# TSOC_USBUART2_R3_0.net
KiCad netlist of a schematic drawn in EAGLE
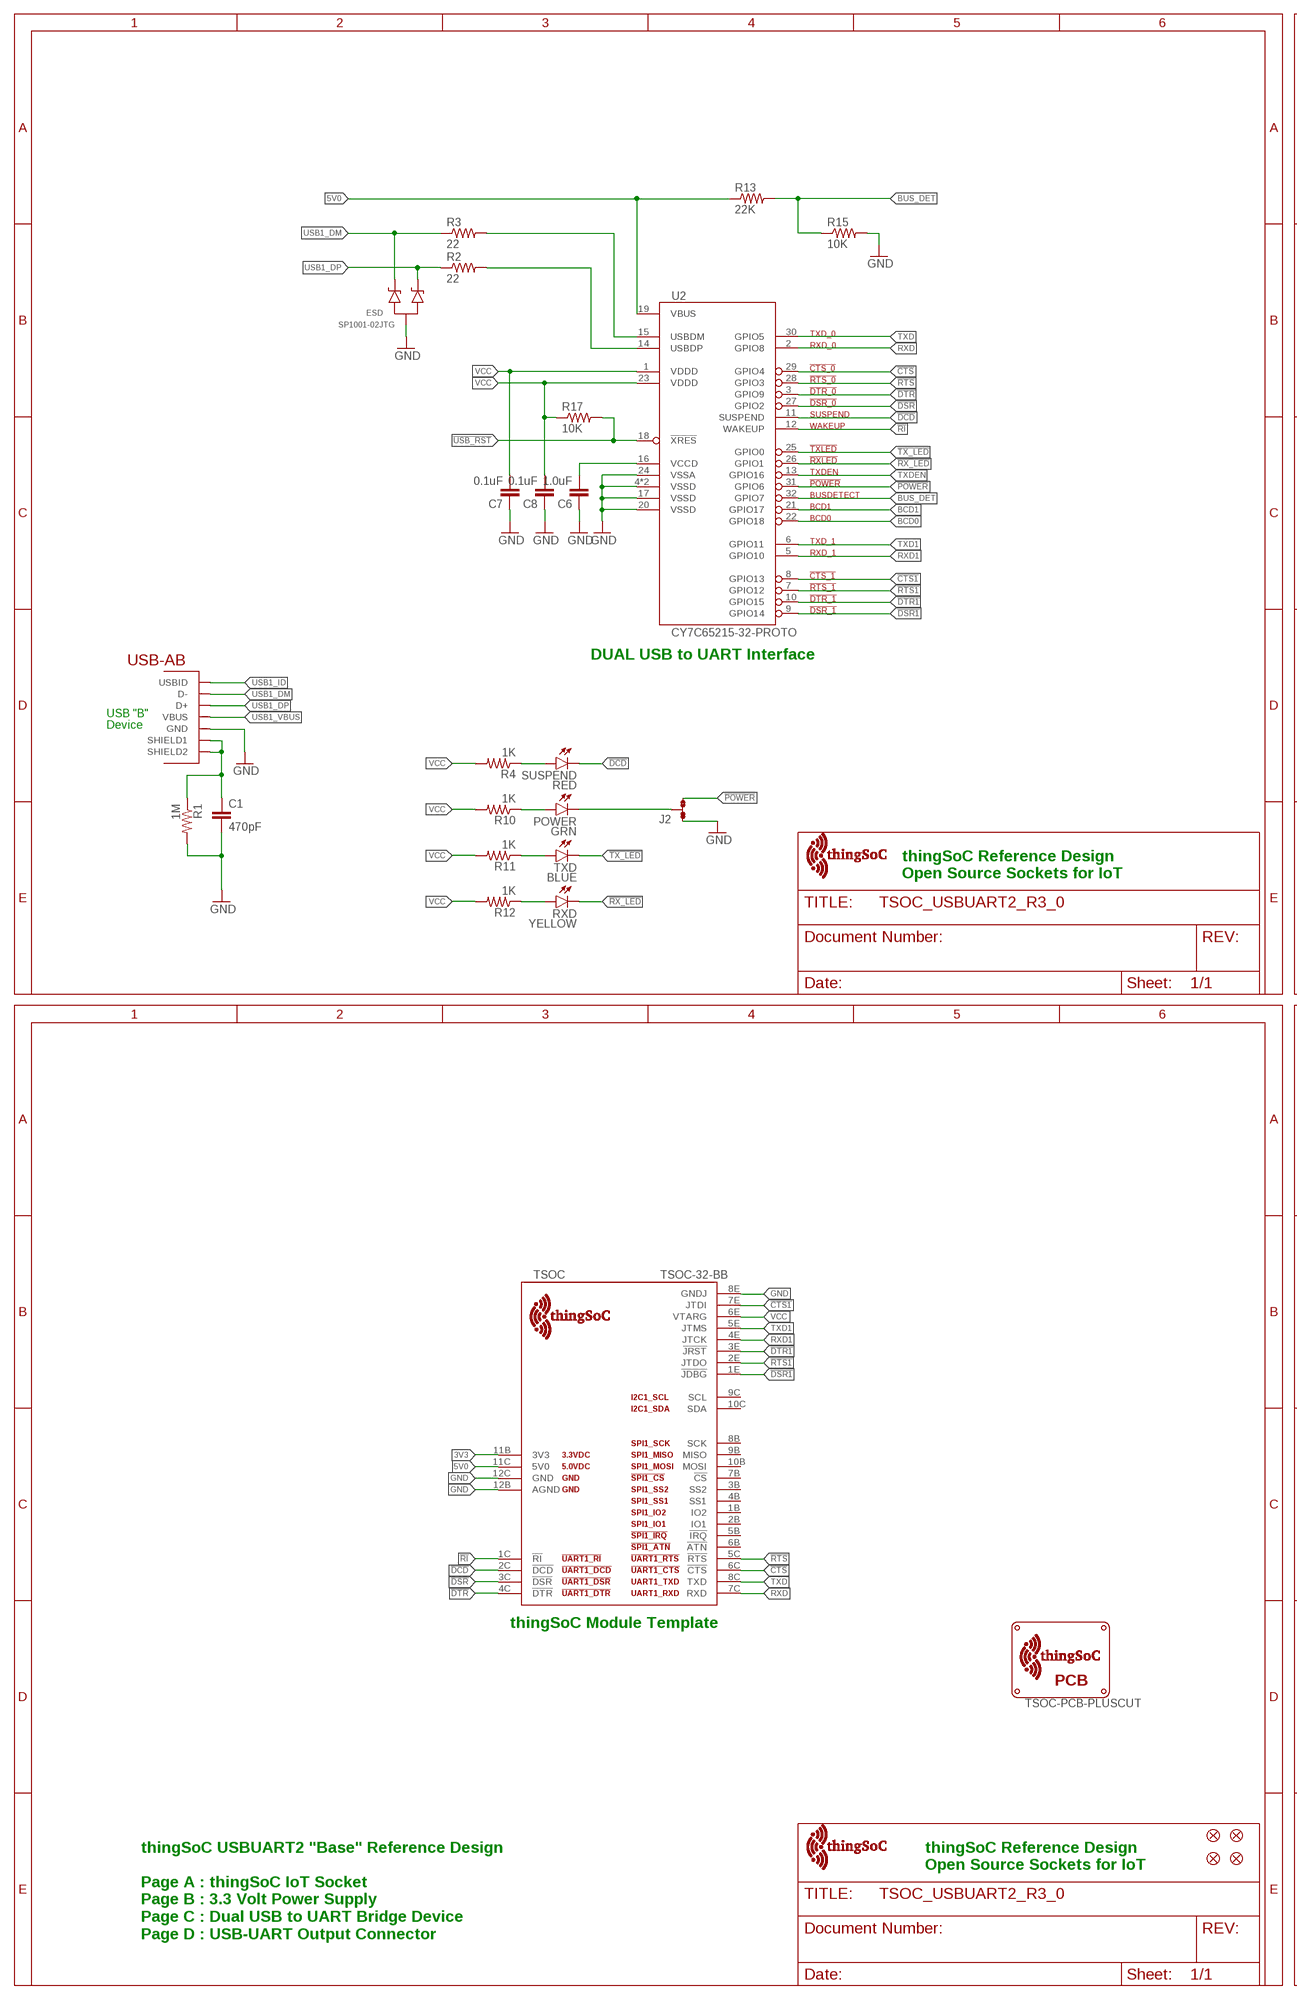
[diagram p0: schematic, sheet 1, part 1 of 2]
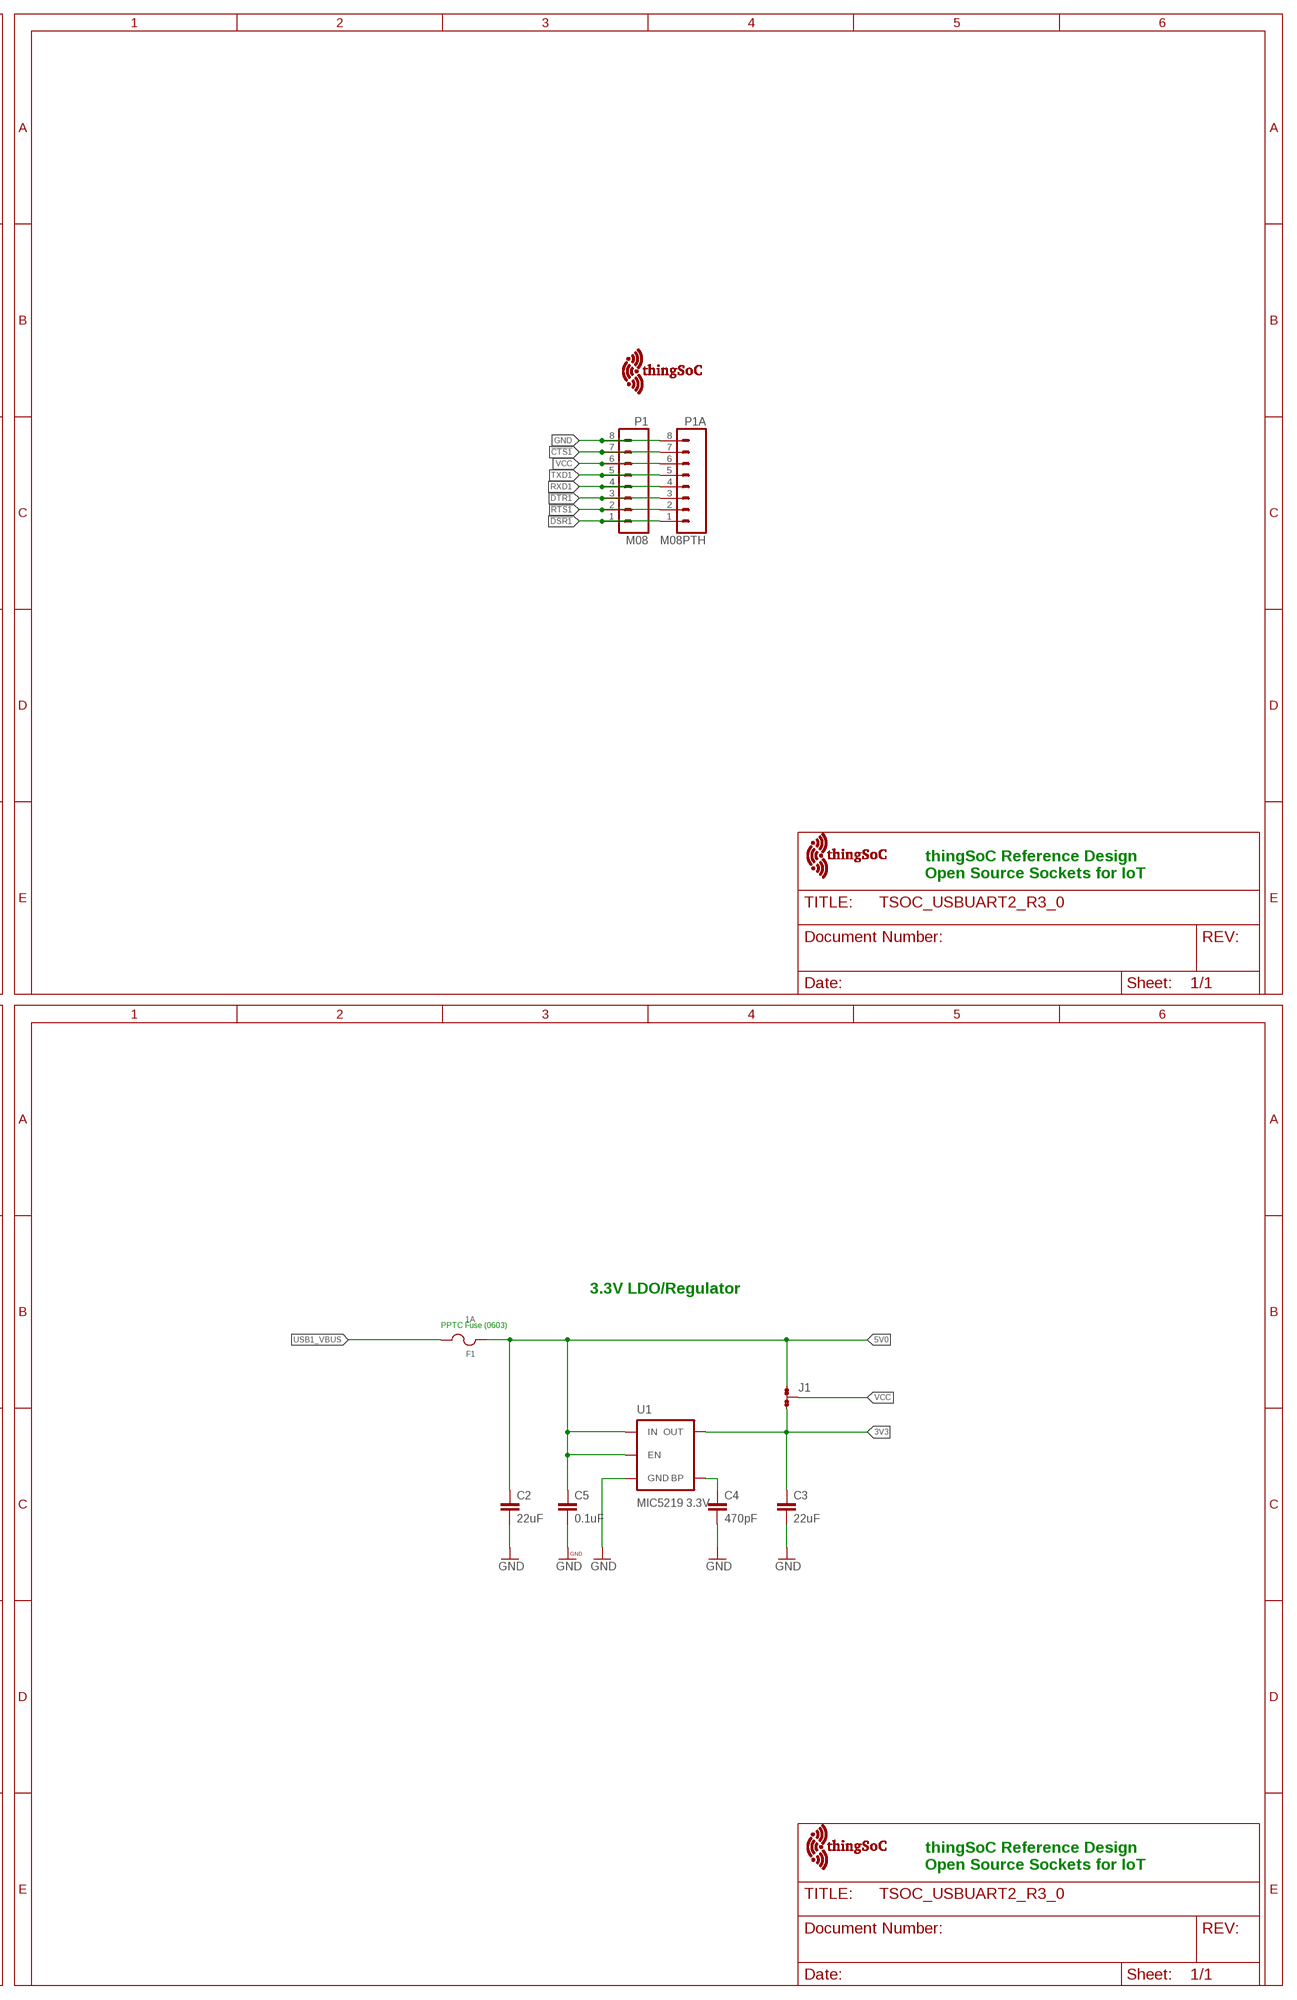
[diagram p1: schematic, sheet 1, part 2 of 2]

(export (version "E")
  (design (tool "Eeschema 10.0.6"))
  (components
    (comp (ref "C1")
      (value "470pF")
      (footprint "eagle-import:EIA-0603")
      (libsource (lib "eagle-import") (part "CAP-0603"))
    )
    (comp (ref "C2")
      (value "22uF")
      (footprint "eagle-import:EIA-1206")
      (libsource (lib "eagle-import") (part "CAP-1206"))
    )
    (comp (ref "C3")
      (value "22uF")
      (footprint "eagle-import:EIA-1206")
      (libsource (lib "eagle-import") (part "CAP-1206"))
    )
    (comp (ref "C4")
      (value "470pF")
      (footprint "eagle-import:EIA-0603")
      (libsource (lib "eagle-import") (part "CAP-0603"))
    )
    (comp (ref "C5")
      (value "0.1uF")
      (footprint "eagle-import:EIA-0603")
      (libsource (lib "eagle-import") (part "CAP-0603"))
    )
    (comp (ref "C6")
      (value "1.0uF")
      (footprint "eagle-import:EIA-0603")
      (libsource (lib "eagle-import") (part "CAP-0603"))
    )
    (comp (ref "C7")
      (value "0.1uF")
      (footprint "eagle-import:EIA-0603")
      (libsource (lib "eagle-import") (part "CAP-0603"))
    )
    (comp (ref "C8")
      (value "0.1uF")
      (footprint "eagle-import:EIA-0603")
      (libsource (lib "eagle-import") (part "CAP-0603"))
    )
    (comp (ref "ESD")
      (value "SP1001-02JTG")
      (footprint "eagle-import:SC70-3")
      (libsource (lib "eagle-import") (part "SP1001-02JTG"))
    )
    (comp (ref "F1")
      (value "1A")
      (footprint "eagle-import:EIA-0603")
      (libsource (lib "eagle-import") (part "FUSE"))
    )
    (comp (ref "FID1")
      (value "FIDUCIALUFIDUCIAL")
      (footprint "eagle-import:MICRO-FIDUCIAL")
      (libsource (lib "eagle-import") (part "FIDUCIALUFIDUCIAL"))
    )
    (comp (ref "FID2")
      (value "FIDUCIALUFIDUCIAL")
      (footprint "eagle-import:MICRO-FIDUCIAL")
      (libsource (lib "eagle-import") (part "FIDUCIALUFIDUCIAL"))
    )
    (comp (ref "FID3")
      (value "FIDUCIALUFIDUCIAL")
      (footprint "eagle-import:MICRO-FIDUCIAL")
      (libsource (lib "eagle-import") (part "FIDUCIALUFIDUCIAL"))
    )
    (comp (ref "FID4")
      (value "FIDUCIALUFIDUCIAL")
      (footprint "eagle-import:MICRO-FIDUCIAL")
      (libsource (lib "eagle-import") (part "FIDUCIALUFIDUCIAL"))
    )
    (comp (ref "J1")
      (value "JMP-3-1_2")
      (footprint "eagle-import:JMP-3-1_2")
      (libsource (lib "eagle-import") (part "JMP-3-1_2"))
    )
    (comp (ref "J2")
      (value "JMP-3-1_2")
      (footprint "eagle-import:JMP-3-1_2")
      (libsource (lib "eagle-import") (part "JMP-3-1_2"))
    )
    (comp (ref "P1")
      (value "M08")
      (footprint "eagle-import:1X08-SMD-FEMALE")
      (libsource (lib "eagle-import") (part "M08"))
    )
    (comp (ref "P1A")
      (value "M08PTH")
      (footprint "eagle-import:1X08")
      (libsource (lib "eagle-import") (part "M08PTH"))
    )
    (comp (ref "POWER")
      (value "GRN")
      (footprint "eagle-import:LED-0603")
      (libsource (lib "eagle-import") (part "LED0603"))
    )
    (comp (ref "R1")
      (value "1M")
      (footprint "eagle-import:EIA-0603")
      (libsource (lib "eagle-import") (part "RESISTOR-0603"))
    )
    (comp (ref "R2")
      (value "22")
      (footprint "eagle-import:EIA-0603")
      (libsource (lib "eagle-import") (part "RESISTOR-0603"))
    )
    (comp (ref "R3")
      (value "22")
      (footprint "eagle-import:EIA-0603")
      (libsource (lib "eagle-import") (part "RESISTOR-0603"))
    )
    (comp (ref "R4")
      (value "1K")
      (footprint "eagle-import:EIA-0603")
      (libsource (lib "eagle-import") (part "RESISTOR-0603"))
    )
    (comp (ref "R10")
      (value "1K")
      (footprint "eagle-import:EIA-0603")
      (libsource (lib "eagle-import") (part "RESISTOR-0603"))
    )
    (comp (ref "R11")
      (value "1K")
      (footprint "eagle-import:EIA-0603")
      (libsource (lib "eagle-import") (part "RESISTOR-0603"))
    )
    (comp (ref "R12")
      (value "1K")
      (footprint "eagle-import:EIA-0603")
      (libsource (lib "eagle-import") (part "RESISTOR-0603"))
    )
    (comp (ref "R13")
      (value "22K")
      (footprint "eagle-import:EIA-0603")
      (libsource (lib "eagle-import") (part "RESISTOR-0603"))
    )
    (comp (ref "R15")
      (value "10K")
      (footprint "eagle-import:EIA-0603")
      (libsource (lib "eagle-import") (part "RESISTOR-0603"))
    )
    (comp (ref "R17")
      (value "10K")
      (footprint "eagle-import:EIA-0603")
      (libsource (lib "eagle-import") (part "RESISTOR-0603"))
    )
    (comp (ref "RXD")
      (value "YELLOW")
      (footprint "eagle-import:LED-0603")
      (libsource (lib "eagle-import") (part "LED0603"))
    )
    (comp (ref "SUSPEND")
      (value "RED")
      (footprint "eagle-import:LED-0603")
      (libsource (lib "eagle-import") (part "LED0603"))
    )
    (comp (ref "TSOC")
      (value "TSOC-32-BB")
      (footprint "eagle-import:TSOC-BB-S32")
      (libsource (lib "eagle-import") (part "TSOC-32-BB"))
    )
    (comp (ref "TXD")
      (value "BLUE")
      (footprint "eagle-import:LED-0603")
      (libsource (lib "eagle-import") (part "LED0603"))
    )
    (comp (ref "U$1")
      (value "TSOC-LOGO-SMALL")
      (footprint "eagle-import:TSOC-LOGO-SML")
      (libsource (lib "eagle-import") (part "TSOC-LOGO-SMALL"))
    )
    (comp (ref "U$3")
      (value "TSOC-LOGO-LRG")
      (footprint "eagle-import:TSOC-LOGO-LRG")
      (libsource (lib "eagle-import") (part "TSOC-LOGO-LRG"))
    )
    (comp (ref "U$4")
      (value "TSOC-LOGO")
      (footprint "eagle-import:TSOC-LOGO-BLANK")
      (libsource (lib "eagle-import") (part "TSOC-LOGO"))
    )
    (comp (ref "U$5")
      (value "TSOC-LOGO")
      (footprint "eagle-import:TSOC-LOGO-BLANK")
      (libsource (lib "eagle-import") (part "TSOC-LOGO"))
    )
    (comp (ref "U$6")
      (value "TSOC-LOGO")
      (footprint "eagle-import:TSOC-LOGO-BLANK")
      (libsource (lib "eagle-import") (part "TSOC-LOGO"))
    )
    (comp (ref "U$7")
      (value "TSOC-PCB-PLUSCUT")
      (footprint "eagle-import:TSOC-BB-BRD-PLUS-CUT")
      (libsource (lib "eagle-import") (part "TSOC-PCB-PLUSCUT"))
    )
    (comp (ref "U1")
      (value "MIC5219 3.3V")
      (footprint "eagle-import:SOT23-5")
      (libsource (lib "eagle-import") (part "V_REG_MIC52193.3V"))
    )
    (comp (ref "U2")
      (value "CY7C65215-32-PROTO")
      (footprint "eagle-import:QFN32-PROTO")
      (libsource (lib "eagle-import") (part "CY7C65215-32-PROTO"))
    )
    (comp (ref "USB")
      (value "USB_AB")
      (footprint "eagle-import:USB-AB-MICRO-SMD")
      (libsource (lib "eagle-import") (part "USB_AB"))
    )
  )
  (nets
    (net (code "1") (name "/~{CTS1}") (class "Default")
      (node (ref "P1") (pin "7") (pinfunction "7_7") (pintype "passive"))
      (node (ref "P1A") (pin "7") (pinfunction "7_7") (pintype "passive"))
      (node (ref "TSOC") (pin "7E") (pinfunction "JTDI_7E") (pintype "bidirectional"))
      (node (ref "U2") (pin "8") (pinfunction "GPIO13_8") (pintype "input"))
    )
    (net (code "2") (name "/~{CTS}") (class "Default")
      (node (ref "TSOC") (pin "6C") (pinfunction "~{CTS}_6C") (pintype "bidirectional"))
      (node (ref "U2") (pin "29") (pinfunction "GPIO4_29") (pintype "input"))
    )
    (net (code "3") (name "/~{DCD}") (class "Default")
      (node (ref "SUSPEND") (pin "C") (pinfunction "C_C") (pintype "passive"))
      (node (ref "TSOC") (pin "2C") (pinfunction "~{DCD}_2C") (pintype "bidirectional"))
      (node (ref "U2") (pin "11") (pinfunction "SUSPEND_11") (pintype "input"))
    )
    (net (code "4") (name "/~{DSR1}") (class "Default")
      (node (ref "P1") (pin "1") (pinfunction "1_1") (pintype "passive"))
      (node (ref "P1A") (pin "1") (pinfunction "1_1") (pintype "passive"))
      (node (ref "TSOC") (pin "1E") (pinfunction "~{JDBG}_1E") (pintype "bidirectional"))
      (node (ref "U2") (pin "9") (pinfunction "GPIO14_9") (pintype "input"))
    )
    (net (code "5") (name "/~{DSR}") (class "Default")
      (node (ref "TSOC") (pin "3C") (pinfunction "~{DSR}_3C") (pintype "bidirectional"))
      (node (ref "U2") (pin "27") (pinfunction "GPIO2_27") (pintype "input"))
    )
    (net (code "6") (name "/~{DTR1}") (class "Default")
      (node (ref "P1") (pin "3") (pinfunction "3_3") (pintype "passive"))
      (node (ref "P1A") (pin "3") (pinfunction "3_3") (pintype "passive"))
      (node (ref "TSOC") (pin "3E") (pinfunction "~{JRST}_3E") (pintype "bidirectional"))
      (node (ref "U2") (pin "10") (pinfunction "GPIO15_10") (pintype "output"))
    )
    (net (code "7") (name "/~{DTR}") (class "Default")
      (node (ref "TSOC") (pin "4C") (pinfunction "~{DTR}_4C") (pintype "bidirectional"))
      (node (ref "U2") (pin "3") (pinfunction "GPIO9_3") (pintype "output"))
    )
    (net (code "8") (name "/~{POWER}") (class "Default")
      (node (ref "J2") (pin "3") (pinfunction "3_3") (pintype "passive"))
      (node (ref "U2") (pin "31") (pinfunction "GPIO6_31") (pintype "input"))
    )
    (net (code "9") (name "/~{RI}") (class "Default")
      (node (ref "TSOC") (pin "1C") (pinfunction "~{RI}_1C") (pintype "bidirectional"))
      (node (ref "U2") (pin "12") (pinfunction "WAKEUP_12") (pintype "input"))
    )
    (net (code "10") (name "/~{RTS1}") (class "Default")
      (node (ref "P1") (pin "2") (pinfunction "2_2") (pintype "passive"))
      (node (ref "P1A") (pin "2") (pinfunction "2_2") (pintype "passive"))
      (node (ref "TSOC") (pin "2E") (pinfunction "JTDO_2E") (pintype "bidirectional"))
      (node (ref "U2") (pin "7") (pinfunction "GPIO12_7") (pintype "output"))
    )
    (net (code "11") (name "/~{RTS}") (class "Default")
      (node (ref "TSOC") (pin "5C") (pinfunction "~{RTS}_5C") (pintype "bidirectional"))
      (node (ref "U2") (pin "28") (pinfunction "GPIO3_28") (pintype "output"))
    )
    (net (code "12") (name "/~{RX_LED}") (class "Default")
      (node (ref "RXD") (pin "C") (pinfunction "C_C") (pintype "passive"))
      (node (ref "U2") (pin "26") (pinfunction "GPIO1_26") (pintype "input"))
    )
    (net (code "13") (name "/~{TX_LED}") (class "Default")
      (node (ref "TXD") (pin "C") (pinfunction "C_C") (pintype "passive"))
      (node (ref "U2") (pin "25") (pinfunction "GPIO0_25") (pintype "input"))
    )
    (net (code "14") (name "/~{USB_RST}") (class "Default")
      (node (ref "R17") (pin "2") (pinfunction "2_2") (pintype "passive"))
      (node (ref "U2") (pin "18") (pinfunction "~{XRES}_18") (pintype "input"))
    )
    (net (code "15") (name "3V3") (class "Default")
      (node (ref "C3") (pin "1") (pinfunction "1_1") (pintype "passive"))
      (node (ref "J1") (pin "3") (pinfunction "3_3") (pintype "passive"))
      (node (ref "TSOC") (pin "11B") (pinfunction "3V3_11B") (pintype "bidirectional"))
      (node (ref "U1") (pin "5") (pinfunction "OUT_5") (pintype "passive"))
    )
    (net (code "16") (name "5V0") (class "Default")
      (node (ref "C2") (pin "1") (pinfunction "1_1") (pintype "passive"))
      (node (ref "C5") (pin "1") (pinfunction "1_1") (pintype "passive"))
      (node (ref "F1") (pin "1") (pinfunction "P$1_1") (pintype "bidirectional"))
      (node (ref "J1") (pin "1") (pinfunction "1_1") (pintype "passive"))
      (node (ref "R13") (pin "1") (pinfunction "1_1") (pintype "passive"))
      (node (ref "TSOC") (pin "11C") (pinfunction "5V0_11C") (pintype "bidirectional"))
      (node (ref "U1") (pin "1") (pinfunction "IN_1") (pintype "input"))
      (node (ref "U1") (pin "3") (pinfunction "EN_3") (pintype "input"))
      (node (ref "U2") (pin "19") (pinfunction "VBUS_19") (pintype "power_in"))
    )
    (net (code "17") (name "BCD0") (class "Default")
      (node (ref "U2") (pin "22") (pinfunction "GPIO18_22") (pintype "input"))
    )
    (net (code "18") (name "BCD1") (class "Default")
      (node (ref "U2") (pin "21") (pinfunction "GPIO17_21") (pintype "input"))
    )
    (net (code "19") (name "BUS_DET") (class "Default")
      (node (ref "R13") (pin "2") (pinfunction "2_2") (pintype "passive"))
      (node (ref "R15") (pin "1") (pinfunction "1_1") (pintype "passive"))
      (node (ref "U2") (pin "32") (pinfunction "GPIO7_32") (pintype "input"))
    )
    (net (code "20") (name "GND") (class "Default")
      (node (ref "C1") (pin "2") (pinfunction "2_2") (pintype "passive"))
      (node (ref "C2") (pin "2") (pinfunction "2_2") (pintype "passive"))
      (node (ref "C3") (pin "2") (pinfunction "2_2") (pintype "passive"))
      (node (ref "C4") (pin "2") (pinfunction "2_2") (pintype "passive"))
      (node (ref "C5") (pin "2") (pinfunction "2_2") (pintype "passive"))
      (node (ref "C6") (pin "1") (pinfunction "1_1") (pintype "passive"))
      (node (ref "C7") (pin "1") (pinfunction "1_1") (pintype "passive"))
      (node (ref "C8") (pin "1") (pinfunction "1_1") (pintype "passive"))
      (node (ref "ESD") (pin "3") (pinfunction "A_3") (pintype "passive"))
      (node (ref "J2") (pin "1") (pinfunction "1_1") (pintype "passive"))
      (node (ref "P1") (pin "8") (pinfunction "8_8") (pintype "passive"))
      (node (ref "P1A") (pin "8") (pinfunction "8_8") (pintype "passive"))
      (node (ref "R1") (pin "2") (pinfunction "2_2") (pintype "passive"))
      (node (ref "R15") (pin "2") (pinfunction "2_2") (pintype "passive"))
      (node (ref "TSOC") (pin "12B") (pinfunction "AGND_12B") (pintype "bidirectional"))
      (node (ref "TSOC") (pin "12C") (pinfunction "GND_12C") (pintype "bidirectional"))
      (node (ref "TSOC") (pin "8E") (pinfunction "GNDJ_8E") (pintype "bidirectional"))
      (node (ref "U1") (pin "2") (pinfunction "GND_2") (pintype "input"))
      (node (ref "U2") (pin "17") (pinfunction "VSSD_17") (pintype "power_in"))
      (node (ref "U2") (pin "20") (pinfunction "VSSD_20") (pintype "power_in"))
      (node (ref "U2") (pin "24") (pinfunction "VSSA_24") (pintype "power_in"))
      (node (ref "U2") (pin "4") (pinfunction "VSSD_4") (pintype "power_in"))
      (node (ref "U2") (pin "EXP") (pinfunction "VSSD_EXP") (pintype "power_in"))
      (node (ref "USB") (pin "GND") (pinfunction "GND_GND") (pintype "bidirectional"))
    )
    (net (code "21") (name "Net-(C1-Pad1)") (class "Default")
      (node (ref "C1") (pin "1") (pinfunction "1_1") (pintype "passive"))
      (node (ref "R1") (pin "1") (pinfunction "1_1") (pintype "passive"))
      (node (ref "USB") (pin "SHIELD1") (pinfunction "SHIELD1_SHIELD1") (pintype "bidirectional"))
      (node (ref "USB") (pin "SHIELD2") (pinfunction "SHIELD2_SHIELD2") (pintype "bidirectional"))
    )
    (net (code "22") (name "Net-(J2-Pad2)") (class "Default")
      (node (ref "J2") (pin "2") (pinfunction "2_2") (pintype "passive"))
      (node (ref "POWER") (pin "C") (pinfunction "C_C") (pintype "passive"))
    )
    (net (code "23") (name "Net-(POWER-PadA)") (class "Default")
      (node (ref "POWER") (pin "A") (pinfunction "A_A") (pintype "passive"))
      (node (ref "R10") (pin "1") (pinfunction "1_1") (pintype "passive"))
    )
    (net (code "24") (name "Net-(R4-Pad1)") (class "Default")
      (node (ref "R4") (pin "1") (pinfunction "1_1") (pintype "passive"))
      (node (ref "SUSPEND") (pin "A") (pinfunction "A_A") (pintype "passive"))
    )
    (net (code "25") (name "Net-(R11-Pad1)") (class "Default")
      (node (ref "R11") (pin "1") (pinfunction "1_1") (pintype "passive"))
      (node (ref "TXD") (pin "A") (pinfunction "A_A") (pintype "passive"))
    )
    (net (code "26") (name "Net-(R12-Pad1)") (class "Default")
      (node (ref "R12") (pin "1") (pinfunction "1_1") (pintype "passive"))
      (node (ref "RXD") (pin "A") (pinfunction "A_A") (pintype "passive"))
    )
    (net (code "27") (name "Net-(U1-BP)") (class "Default")
      (node (ref "C4") (pin "1") (pinfunction "1_1") (pintype "passive"))
      (node (ref "U1") (pin "4") (pinfunction "BP_4") (pintype "input"))
    )
    (net (code "28") (name "Net-(U2-USBDM)") (class "Default")
      (node (ref "R3") (pin "2") (pinfunction "2_2") (pintype "passive"))
      (node (ref "U2") (pin "15") (pinfunction "USBDM_15") (pintype "bidirectional"))
    )
    (net (code "29") (name "Net-(U2-USBDP)") (class "Default")
      (node (ref "R2") (pin "2") (pinfunction "2_2") (pintype "passive"))
      (node (ref "U2") (pin "14") (pinfunction "USBDP_14") (pintype "bidirectional"))
    )
    (net (code "30") (name "Net-(U2-VCCD)") (class "Default")
      (node (ref "C6") (pin "2") (pinfunction "2_2") (pintype "passive"))
      (node (ref "U2") (pin "16") (pinfunction "VCCD_16") (pintype "output"))
    )
    (net (code "31") (name "RXD") (class "Default")
      (node (ref "TSOC") (pin "7C") (pinfunction "RXD_7C") (pintype "bidirectional"))
      (node (ref "U2") (pin "2") (pinfunction "GPIO8_2") (pintype "input"))
    )
    (net (code "32") (name "RXD1") (class "Default")
      (node (ref "P1") (pin "4") (pinfunction "4_4") (pintype "passive"))
      (node (ref "P1A") (pin "4") (pinfunction "4_4") (pintype "passive"))
      (node (ref "TSOC") (pin "4E") (pinfunction "JTCK_4E") (pintype "bidirectional"))
      (node (ref "U2") (pin "5") (pinfunction "GPIO10_5") (pintype "input"))
    )
    (net (code "33") (name "TXD") (class "Default")
      (node (ref "TSOC") (pin "8C") (pinfunction "TXD_8C") (pintype "bidirectional"))
      (node (ref "U2") (pin "30") (pinfunction "GPIO5_30") (pintype "output"))
    )
    (net (code "34") (name "TXD1") (class "Default")
      (node (ref "P1") (pin "5") (pinfunction "5_5") (pintype "passive"))
      (node (ref "P1A") (pin "5") (pinfunction "5_5") (pintype "passive"))
      (node (ref "TSOC") (pin "5E") (pinfunction "JTMS_5E") (pintype "bidirectional"))
      (node (ref "U2") (pin "6") (pinfunction "GPIO11_6") (pintype "output"))
    )
    (net (code "35") (name "TXDEN") (class "Default")
      (node (ref "U2") (pin "13") (pinfunction "GPIO16_13") (pintype "output"))
    )
    (net (code "36") (name "USB1_DM") (class "Default")
      (node (ref "ESD") (pin "2") (pinfunction "C2_2") (pintype "passive"))
      (node (ref "R3") (pin "1") (pinfunction "1_1") (pintype "passive"))
      (node (ref "USB") (pin "D-") (pinfunction "D-_D-") (pintype "bidirectional"))
    )
    (net (code "37") (name "USB1_DP") (class "Default")
      (node (ref "ESD") (pin "1") (pinfunction "C1_1") (pintype "passive"))
      (node (ref "R2") (pin "1") (pinfunction "1_1") (pintype "passive"))
      (node (ref "USB") (pin "D+") (pinfunction "D+_D+") (pintype "bidirectional"))
    )
    (net (code "38") (name "USB1_ID") (class "Default")
      (node (ref "USB") (pin "ID") (pinfunction "USBID_ID") (pintype "bidirectional"))
    )
    (net (code "39") (name "USB1_VBUS") (class "Default")
      (node (ref "F1") (pin "2") (pinfunction "P$2_2") (pintype "bidirectional"))
      (node (ref "USB") (pin "VBUS") (pinfunction "VBUS_VBUS") (pintype "bidirectional"))
    )
    (net (code "40") (name "VCC") (class "Default")
      (node (ref "C7") (pin "2") (pinfunction "2_2") (pintype "passive"))
      (node (ref "C8") (pin "2") (pinfunction "2_2") (pintype "passive"))
      (node (ref "J1") (pin "2") (pinfunction "2_2") (pintype "passive"))
      (node (ref "P1") (pin "6") (pinfunction "6_6") (pintype "passive"))
      (node (ref "P1A") (pin "6") (pinfunction "6_6") (pintype "passive"))
      (node (ref "R10") (pin "2") (pinfunction "2_2") (pintype "passive"))
      (node (ref "R11") (pin "2") (pinfunction "2_2") (pintype "passive"))
      (node (ref "R12") (pin "2") (pinfunction "2_2") (pintype "passive"))
      (node (ref "R17") (pin "1") (pinfunction "1_1") (pintype "passive"))
      (node (ref "R4") (pin "2") (pinfunction "2_2") (pintype "passive"))
      (node (ref "TSOC") (pin "6E") (pinfunction "VTARG_6E") (pintype "bidirectional"))
      (node (ref "U2") (pin "1") (pinfunction "VDDD_1") (pintype "power_in"))
      (node (ref "U2") (pin "23") (pinfunction "VDDD_23") (pintype "power_in"))
    )
    (net (code "41") (name "unconnected-(TSOC-IO1-Pad2B)") (class "Default")
      (node (ref "TSOC") (pin "2B") (pinfunction "IO1_2B") (pintype "bidirectional"))
    )
    (net (code "42") (name "unconnected-(TSOC-IO2-Pad1B)") (class "Default")
      (node (ref "TSOC") (pin "1B") (pinfunction "IO2_1B") (pintype "bidirectional"))
    )
    (net (code "43") (name "unconnected-(TSOC-MISO-Pad9B)") (class "Default")
      (node (ref "TSOC") (pin "9B") (pinfunction "MISO_9B") (pintype "bidirectional"))
    )
    (net (code "44") (name "unconnected-(TSOC-MOSI-Pad10B)") (class "Default")
      (node (ref "TSOC") (pin "10B") (pinfunction "MOSI_10B") (pintype "bidirectional"))
    )
    (net (code "45") (name "unconnected-(TSOC-SCK-Pad8B)") (class "Default")
      (node (ref "TSOC") (pin "8B") (pinfunction "SCK_8B") (pintype "bidirectional"))
    )
    (net (code "46") (name "unconnected-(TSOC-SCL-Pad9C)") (class "Default")
      (node (ref "TSOC") (pin "9C") (pinfunction "SCL_9C") (pintype "bidirectional"))
    )
    (net (code "47") (name "unconnected-(TSOC-SDA-Pad10C)") (class "Default")
      (node (ref "TSOC") (pin "10C") (pinfunction "SDA_10C") (pintype "bidirectional"))
    )
    (net (code "48") (name "unconnected-(TSOC-SS1-Pad4B)") (class "Default")
      (node (ref "TSOC") (pin "4B") (pinfunction "SS1_4B") (pintype "bidirectional"))
    )
    (net (code "49") (name "unconnected-(TSOC-SS2-Pad3B)") (class "Default")
      (node (ref "TSOC") (pin "3B") (pinfunction "SS2_3B") (pintype "bidirectional"))
    )
    (net (code "50") (name "unconnected-(TSOC-~{ATN}-Pad6B)") (class "Default")
      (node (ref "TSOC") (pin "6B") (pinfunction "~{ATN}_6B") (pintype "bidirectional"))
    )
    (net (code "51") (name "unconnected-(TSOC-~{CS}-Pad7B)") (class "Default")
      (node (ref "TSOC") (pin "7B") (pinfunction "~{CS}_7B") (pintype "bidirectional"))
    )
    (net (code "52") (name "unconnected-(TSOC-~{IRQ}-Pad5B)") (class "Default")
      (node (ref "TSOC") (pin "5B") (pinfunction "~{IRQ}_5B") (pintype "bidirectional"))
    )
  )
)
